# Output_Driver.net
KiCad netlist of a schematic drawn in Altium Designer
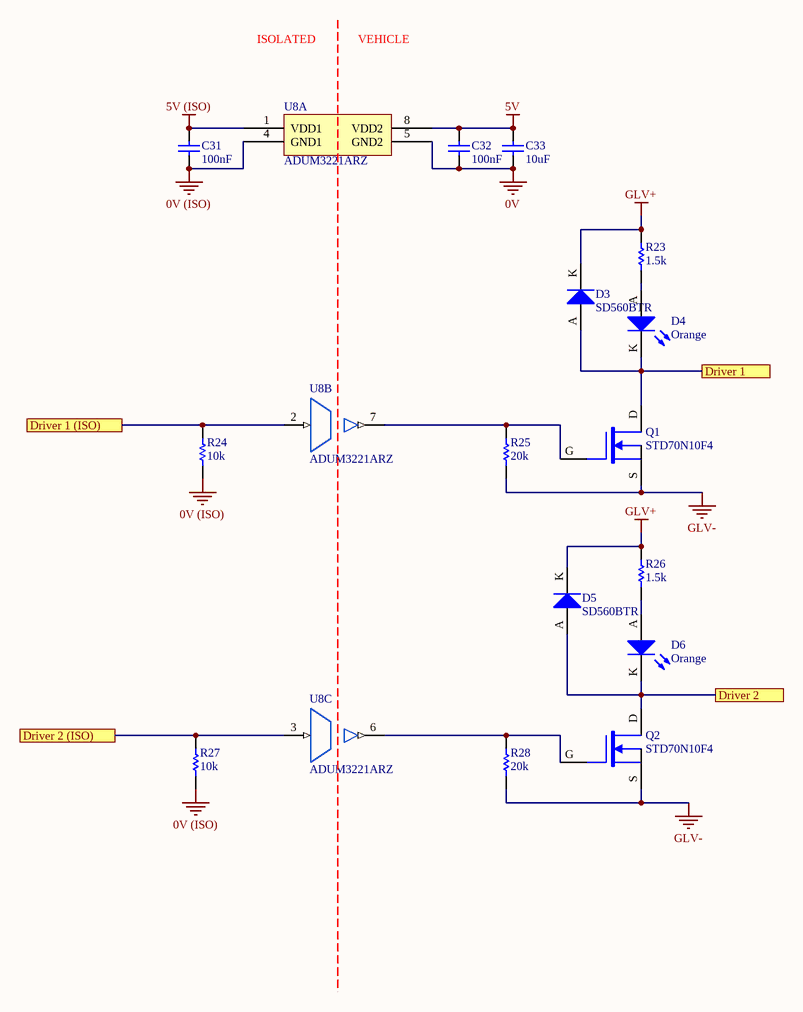
[diagram p0: Output Driver.SchDoc]

(export (version "E")
  (design (tool "Eeschema 10.0.6"))
  (components
    (comp (ref "C31")
      (value "100nF")
      (footprint "0805")
      (fields
        (field (name "PART NUMBER") "GCM21BR71E104KA37L")
        (field (name "TOLERANCE") "10%")
        (field (name "MANUFACTURER") "muRata")
      )
      (libsource (lib "ts_20-standard-library") (part "Capacitor"))
    )
    (comp (ref "C32")
      (value "100nF")
      (footprint "0805")
      (fields
        (field (name "PART NUMBER") "GCM21BR71E104KA37L")
        (field (name "TOLERANCE") "10%")
        (field (name "MANUFACTURER") "muRata")
      )
      (libsource (lib "ts_20-standard-library") (part "Capacitor"))
    )
    (comp (ref "C33")
      (value "10uF")
      (footprint "0805")
      (fields
        (field (name "PART NUMBER") "GRM21BR6YA106KE43L")
        (field (name "TOLERANCE") "10%")
        (field (name "MANUFACTURER") "muRata")
      )
      (libsource (lib "ts_20-standard-library") (part "Capacitor"))
    )
    (comp (ref "D3")
      (value "SD560BTR")
      (footprint "SMB Diode")
      (description "1.2V_F 600V 5A SMB")
      (fields
        (field (name "MANUFACTURER") "SMC Diode Solutions")
        (field (name "DIGIKEY PART NUMBER") "1655-1530-2-ND")
      )
      (libsource (lib "ts_20-standard-library") (part "Diode"))
    )
    (comp (ref "D4")
      (value "Orange")
      (footprint "0805 LED")
      (description "Orange LED Indication - Discrete 1.75V 0805 (2012 Metric)")
      (fields (field (name "PART NUMBER") "SML-211DTT86") (field (name "MANUFACTURER") "ROHM Semiconductor"))
      (libsource (lib "ts_20-standard-library") (part "LED"))
    )
    (comp (ref "D5")
      (value "SD560BTR")
      (footprint "SMB Diode")
      (description "1.2V_F 600V 5A SMB")
      (fields
        (field (name "MANUFACTURER") "SMC Diode Solutions")
        (field (name "DIGIKEY PART NUMBER") "1655-1530-2-ND")
      )
      (libsource (lib "ts_20-standard-library") (part "Diode"))
    )
    (comp (ref "D6")
      (value "Orange")
      (footprint "0805 LED")
      (description "Orange LED Indication - Discrete 1.75V 0805 (2012 Metric)")
      (fields (field (name "PART NUMBER") "SML-211DTT86") (field (name "MANUFACTURER") "ROHM Semiconductor"))
      (libsource (lib "ts_20-standard-library") (part "LED"))
    )
    (comp (ref "Q1")
      (value "STD70N10F4")
      (footprint "STM TO-252 MOSFET")
      (description "N-Channel 100V 60A (Tc) 125W (Tc) Surface Mount DPAK")
      (fields
        (field (name "MANUFACTURER") "STMicroelectronics")
        (field (name "DIGIKEY PART NUMBER") "497-8806-2-ND")
        (field (name "PUBLISHER") "Altium Limited")
      )
      (libsource (lib "ts_20-standard-library") (part "MOSFET-N"))
    )
    (comp (ref "Q2")
      (value "STD70N10F4")
      (footprint "STM TO-252 MOSFET")
      (description "N-Channel 100V 60A (Tc) 125W (Tc) Surface Mount DPAK")
      (fields
        (field (name "MANUFACTURER") "STMicroelectronics")
        (field (name "DIGIKEY PART NUMBER") "497-8806-2-ND")
        (field (name "PUBLISHER") "Altium Limited")
      )
      (libsource (lib "ts_20-standard-library") (part "MOSFET-N"))
    )
    (comp (ref "R23")
      (value "1.5k")
      (footprint "0805")
      (fields
        (field (name "PART NUMBER") "RC0805FR071K5L")
        (field (name "MANUFACTURER") "YAGEO")
        (field (name "TOLERANCE") "0.01")
      )
      (libsource (lib "ts_20-standard-library") (part "Resistor"))
    )
    (comp (ref "R24")
      (value "10k")
      (footprint "0805")
      (fields
        (field (name "PART NUMBER") "RC0805FR0710KL")
        (field (name "MANUFACTURER") "YAGEO")
        (field (name "TOLERANCE") "0.01")
      )
      (libsource (lib "ts_20-standard-library") (part "Resistor"))
    )
    (comp (ref "R25")
      (value "20k")
      (footprint "0805")
      (fields
        (field (name "PART NUMBER") "RC0805FR0720KL")
        (field (name "MANUFACTURER") "YAGEO")
        (field (name "TOLERANCE") "0.01")
      )
      (libsource (lib "ts_20-standard-library") (part "Resistor"))
    )
    (comp (ref "R26")
      (value "1.5k")
      (footprint "0805")
      (fields
        (field (name "PART NUMBER") "RC0805FR071K5L")
        (field (name "MANUFACTURER") "YAGEO")
        (field (name "TOLERANCE") "0.01")
      )
      (libsource (lib "ts_20-standard-library") (part "Resistor"))
    )
    (comp (ref "R27")
      (value "10k")
      (footprint "0805")
      (fields
        (field (name "PART NUMBER") "RC0805FR0710KL")
        (field (name "MANUFACTURER") "YAGEO")
        (field (name "TOLERANCE") "0.01")
      )
      (libsource (lib "ts_20-standard-library") (part "Resistor"))
    )
    (comp (ref "R28")
      (value "20k")
      (footprint "0805")
      (fields
        (field (name "PART NUMBER") "RC0805FR0720KL")
        (field (name "MANUFACTURER") "YAGEO")
        (field (name "TOLERANCE") "0.01")
      )
      (libsource (lib "ts_20-standard-library") (part "Resistor"))
    )
    (comp (ref "U8")
      (value "ADUM3221ARZ")
      (footprint "AD 8-SOIC")
      (description "4A Gate Driver Magnetic Coupling 2500Vrms 2 Channel 8-SOIC")
      (fields
        (field (name "MANUFACTURER") "Analog Devices")
        (field (name "DIGIKEY PART NUMBER") "ADUM3221ARZ-ND")
      )
      (libsource (lib "ts_20-standard-library") (part "ADuM3221"))
    )
  )
  (nets
    (net (code "1") (name "/Driver 1") (class "Default")
      (node (ref "D3") (pin "A") (pinfunction "A_A") (pintype "passive"))
      (node (ref "D4") (pin "K") (pinfunction "K_K") (pintype "passive"))
      (node (ref "Q1") (pin "D") (pinfunction "D_D") (pintype "passive"))
    )
    (net (code "2") (name "/Driver 1 (ISO)") (class "Default")
      (node (ref "R24") (pin "2") (pinfunction "2_2") (pintype "passive"))
      (node (ref "U8") (pin "2") (pinfunction "VIA_2") (pintype "input"))
    )
    (net (code "3") (name "/Driver 2") (class "Default")
      (node (ref "D5") (pin "A") (pinfunction "A_A") (pintype "passive"))
      (node (ref "D6") (pin "K") (pinfunction "K_K") (pintype "passive"))
      (node (ref "Q2") (pin "D") (pinfunction "D_D") (pintype "passive"))
    )
    (net (code "4") (name "/Driver 2 (ISO)") (class "Default")
      (node (ref "R27") (pin "2") (pinfunction "2_2") (pintype "passive"))
      (node (ref "U8") (pin "3") (pinfunction "VIA_3") (pintype "input"))
    )
    (net (code "5") (name "0V") (class "Default")
      (node (ref "C32") (pin "1") (pinfunction "1_1") (pintype "passive"))
      (node (ref "C33") (pin "1") (pinfunction "1_1") (pintype "passive"))
      (node (ref "U8") (pin "5") (pinfunction "GND2_5") (pintype "passive"))
    )
    (net (code "6") (name "0V (ISO)") (class "Default")
      (node (ref "C31") (pin "1") (pinfunction "1_1") (pintype "passive"))
      (node (ref "R24") (pin "1") (pinfunction "1_1") (pintype "passive"))
      (node (ref "R27") (pin "1") (pinfunction "1_1") (pintype "passive"))
      (node (ref "U8") (pin "4") (pinfunction "GND1_4") (pintype "passive"))
    )
    (net (code "7") (name "5V") (class "Default")
      (node (ref "C32") (pin "2") (pinfunction "2_2") (pintype "passive"))
      (node (ref "C33") (pin "2") (pinfunction "2_2") (pintype "passive"))
      (node (ref "U8") (pin "8") (pinfunction "VDD2_8") (pintype "passive"))
    )
    (net (code "8") (name "5V (ISO)") (class "Default")
      (node (ref "C31") (pin "2") (pinfunction "2_2") (pintype "passive"))
      (node (ref "U8") (pin "1") (pinfunction "VDD1_1") (pintype "passive"))
    )
    (net (code "9") (name "GLV+") (class "Default")
      (node (ref "D3") (pin "K") (pinfunction "K_K") (pintype "passive"))
      (node (ref "D5") (pin "K") (pinfunction "K_K") (pintype "passive"))
      (node (ref "R23") (pin "2") (pinfunction "2_2") (pintype "passive"))
      (node (ref "R26") (pin "2") (pinfunction "2_2") (pintype "passive"))
    )
    (net (code "10") (name "GLV-") (class "Default")
      (node (ref "Q1") (pin "S") (pinfunction "S_S") (pintype "passive"))
      (node (ref "Q2") (pin "S") (pinfunction "S_S") (pintype "passive"))
      (node (ref "R25") (pin "1") (pinfunction "1_1") (pintype "passive"))
      (node (ref "R28") (pin "1") (pinfunction "1_1") (pintype "passive"))
    )
    (net (code "11") (name "Net-(D4-PadA)") (class "Default")
      (node (ref "D4") (pin "A") (pinfunction "A_A") (pintype "passive"))
      (node (ref "R23") (pin "1") (pinfunction "1_1") (pintype "passive"))
    )
    (net (code "12") (name "Net-(D6-PadA)") (class "Default")
      (node (ref "D6") (pin "A") (pinfunction "A_A") (pintype "passive"))
      (node (ref "R26") (pin "1") (pinfunction "1_1") (pintype "passive"))
    )
    (net (code "13") (name "Net-(U8B-VOA)") (class "Default")
      (node (ref "Q1") (pin "G") (pinfunction "G_G") (pintype "passive"))
      (node (ref "R25") (pin "2") (pinfunction "2_2") (pintype "passive"))
      (node (ref "U8") (pin "7") (pinfunction "VOA_7") (pintype "output"))
    )
    (net (code "14") (name "Net-(U8C-VOA)") (class "Default")
      (node (ref "Q2") (pin "G") (pinfunction "G_G") (pintype "passive"))
      (node (ref "R28") (pin "2") (pinfunction "2_2") (pintype "passive"))
      (node (ref "U8") (pin "6") (pinfunction "VOA_6") (pintype "output"))
    )
  )
)
